# rgbboard.net
KiCad netlist of a schematic drawn in EAGLE
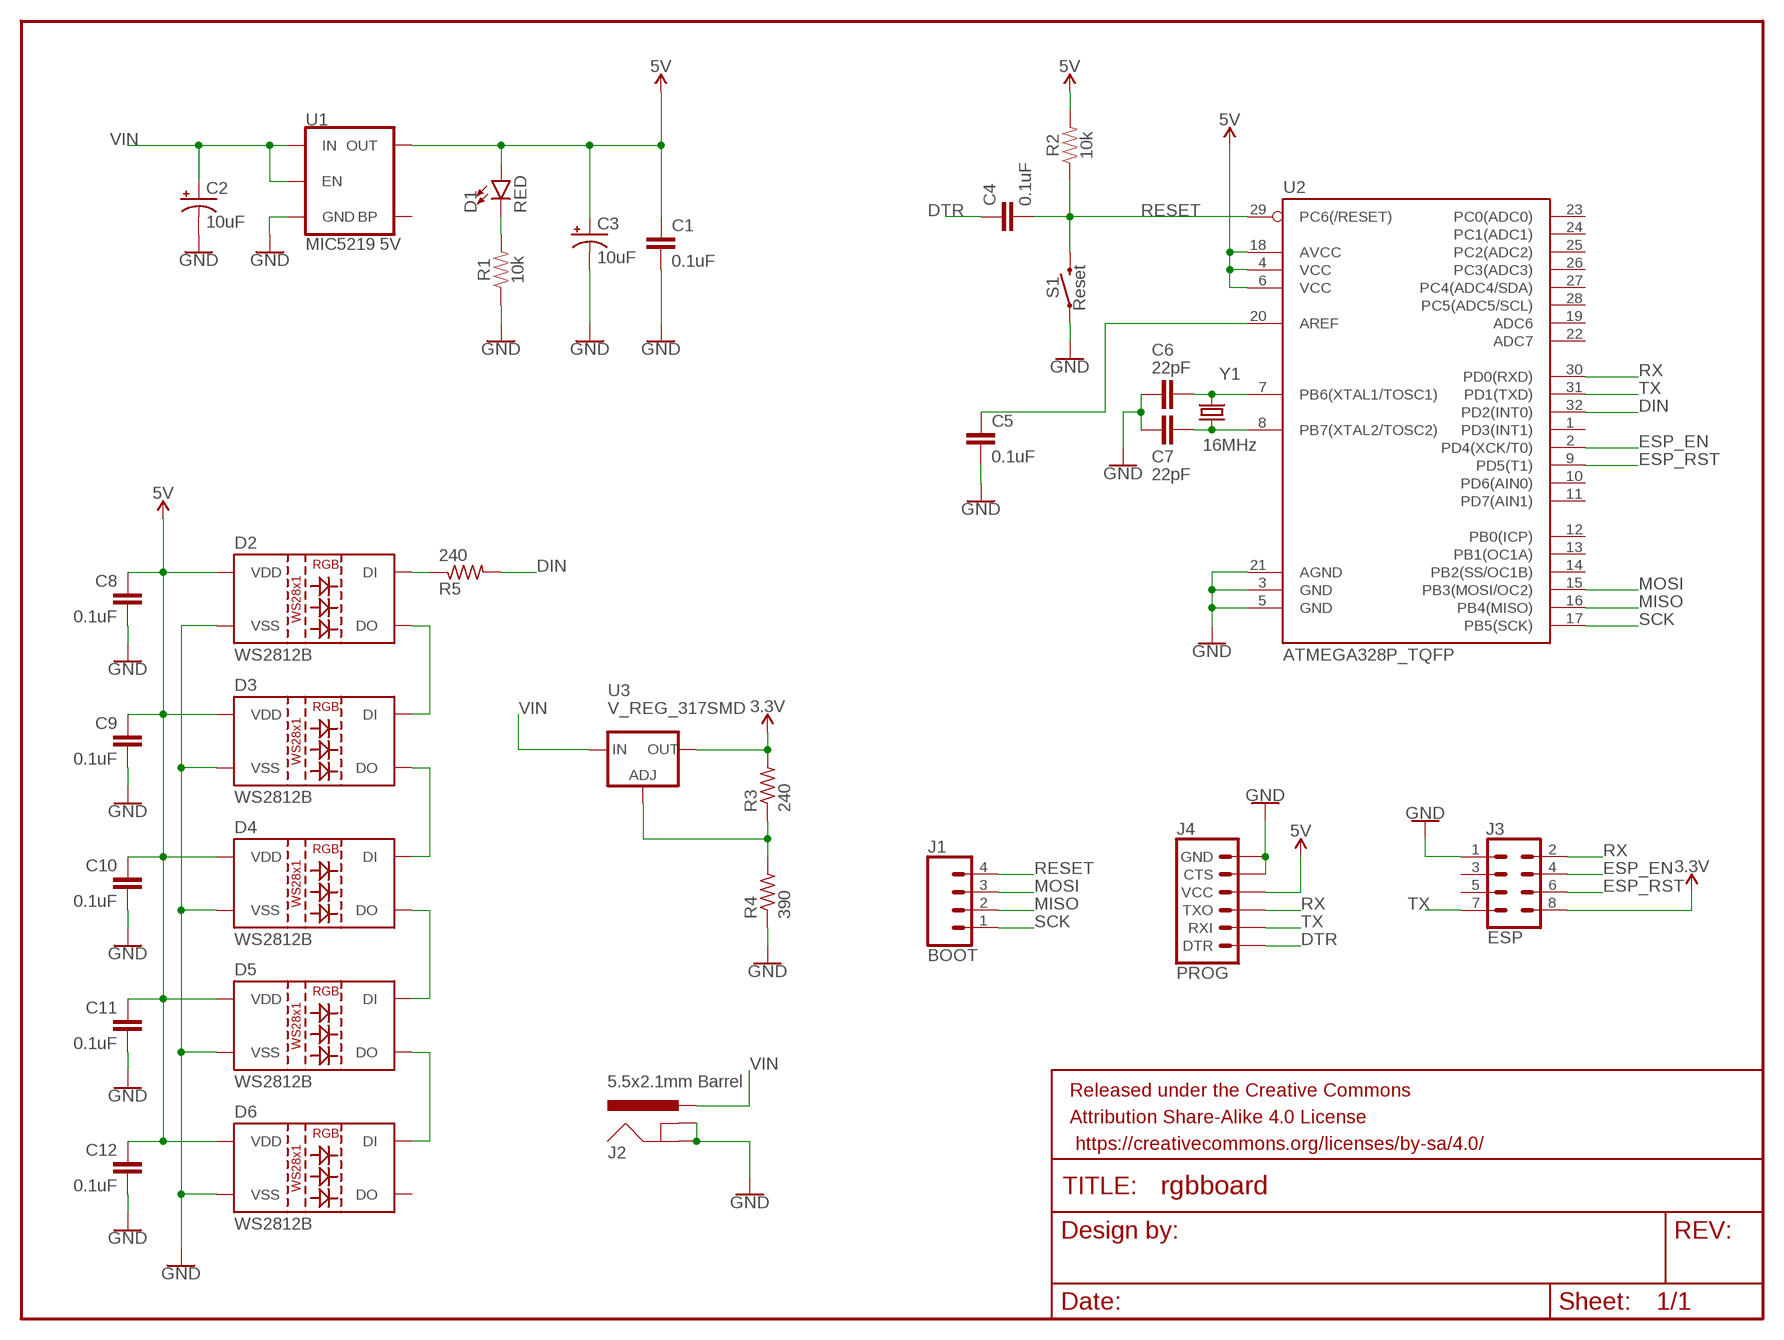
[diagram p0: schematic, sheet 1]

(export (version "E")
  (design (tool "Eeschema 10.0.6"))
  (components
    (comp (ref "C1")
      (value "0.1uF")
      (footprint "eagle-import:0603")
      (libsource (lib "eagle-import") (part "0.1UF-0603-25V-5%"))
    )
    (comp (ref "C2")
      (value "10uF")
      (footprint "eagle-import:EIA3216")
      (libsource (lib "eagle-import") (part "10UF-POLAR-EIA3216-16V-10%(TANT)"))
    )
    (comp (ref "C3")
      (value "10uF")
      (footprint "eagle-import:EIA3216")
      (libsource (lib "eagle-import") (part "10UF-POLAR-EIA3216-16V-10%(TANT)"))
    )
    (comp (ref "C4")
      (value "0.1uF")
      (footprint "eagle-import:0603")
      (libsource (lib "eagle-import") (part "0.1UF-0603-25V-5%"))
    )
    (comp (ref "C5")
      (value "0.1uF")
      (footprint "eagle-import:0603")
      (libsource (lib "eagle-import") (part "0.1UF-0603-25V-5%"))
    )
    (comp (ref "C6")
      (value "22pF")
      (footprint "eagle-import:0603")
      (libsource (lib "eagle-import") (part "22PF-0603-50V-5%"))
    )
    (comp (ref "C7")
      (value "22pF")
      (footprint "eagle-import:0603")
      (libsource (lib "eagle-import") (part "22PF-0603-50V-5%"))
    )
    (comp (ref "C8")
      (value "0.1uF")
      (footprint "eagle-import:0603")
      (libsource (lib "eagle-import") (part "0.1UF-0603-25V-5%"))
    )
    (comp (ref "C9")
      (value "0.1uF")
      (footprint "eagle-import:0603")
      (libsource (lib "eagle-import") (part "0.1UF-0603-25V-5%"))
    )
    (comp (ref "C10")
      (value "0.1uF")
      (footprint "eagle-import:0603")
      (libsource (lib "eagle-import") (part "0.1UF-0603-25V-5%"))
    )
    (comp (ref "C11")
      (value "0.1uF")
      (footprint "eagle-import:0603")
      (libsource (lib "eagle-import") (part "0.1UF-0603-25V-5%"))
    )
    (comp (ref "C12")
      (value "0.1uF")
      (footprint "eagle-import:0603")
      (libsource (lib "eagle-import") (part "0.1UF-0603-25V-5%"))
    )
    (comp (ref "D1")
      (value "RED")
      (footprint "eagle-import:LED-0603")
      (libsource (lib "eagle-import") (part "LED-RED0603"))
    )
    (comp (ref "D2")
      (value "WS2812B")
      (footprint "eagle-import:WS2812B")
      (libsource (lib "eagle-import") (part "WS2812B"))
    )
    (comp (ref "D3")
      (value "WS2812B")
      (footprint "eagle-import:WS2812B")
      (libsource (lib "eagle-import") (part "WS2812B"))
    )
    (comp (ref "D4")
      (value "WS2812B")
      (footprint "eagle-import:WS2812B")
      (libsource (lib "eagle-import") (part "WS2812B"))
    )
    (comp (ref "D5")
      (value "WS2812B")
      (footprint "eagle-import:WS2812B")
      (libsource (lib "eagle-import") (part "WS2812B"))
    )
    (comp (ref "D6")
      (value "WS2812B")
      (footprint "eagle-import:WS2812B")
      (libsource (lib "eagle-import") (part "WS2812B"))
    )
    (comp (ref "FRAME1")
      (value "FRAME-LETTER")
      (footprint "eagle-import:CREATIVE_COMMONS")
      (libsource (lib "eagle-import") (part "FRAME-LETTER"))
    )
    (comp (ref "J1")
      (value "BOOT")
      (footprint "eagle-import:1X04")
      (libsource (lib "eagle-import") (part "CONN_04"))
    )
    (comp (ref "J2")
      (value "5.5x2.1mm Barrel")
      (footprint "eagle-import:POWER_JACK_SMD")
      (libsource (lib "eagle-import") (part "POWER_JACKSMD"))
    )
    (comp (ref "J3")
      (value "ESP")
      (footprint "eagle-import:2X4")
      (libsource (lib "eagle-import") (part "CONN_04X2"))
    )
    (comp (ref "J4")
      (value "PROG")
      (footprint "eagle-import:1X06")
      (libsource (lib "eagle-import") (part "6_PIN_SERIAL_TARGET"))
    )
    (comp (ref "R1")
      (value "10k")
      (footprint "eagle-import:0603")
      (libsource (lib "eagle-import") (part "10KOHM-0603-1/10W-1%"))
    )
    (comp (ref "R2")
      (value "10k")
      (footprint "eagle-import:0603")
      (libsource (lib "eagle-import") (part "10KOHM-0603-1/10W-1%"))
    )
    (comp (ref "R3")
      (value "240")
      (footprint "eagle-import:R0603")
      (libsource (lib "eagle-import") (part "R-US_R0603"))
    )
    (comp (ref "R4")
      (value "390")
      (footprint "eagle-import:R0603")
      (libsource (lib "eagle-import") (part "R-US_R0603"))
    )
    (comp (ref "R5")
      (value "240")
      (footprint "eagle-import:R0603")
      (libsource (lib "eagle-import") (part "R-US_R0603"))
    )
    (comp (ref "S1")
      (value "Reset")
      (footprint "eagle-import:TACTILE_SWITCH_SMD_5.2MM")
      (libsource (lib "eagle-import") (part "MOMENTARY-SWITCH-SPST-SMD-5.2-REDUNDANT"))
    )
    (comp (ref "U1")
      (value "MIC5219 5V")
      (footprint "eagle-import:SOT23-5")
      (libsource (lib "eagle-import") (part "V_REG_MIC52195V"))
    )
    (comp (ref "U2")
      (value "ATMEGA328P_TQFP")
      (footprint "eagle-import:TQFP32-08")
      (libsource (lib "eagle-import") (part "ATMEGA328P_TQFP"))
    )
    (comp (ref "U3")
      (value "V_REG_317SMD")
      (footprint "eagle-import:SOT223")
      (libsource (lib "eagle-import") (part "V_REG_317SMD"))
    )
    (comp (ref "Y1")
      (value "16MHz")
      (footprint "eagle-import:CRYSTAL-SMD-5X3.2-4PAD")
      (libsource (lib "eagle-import") (part "CRYSTAL-16MHZSMD-5X3.2"))
    )
  )
  (nets
    (net (code "1") (name "/DIN") (class "Default")
      (node (ref "R5") (pin "2") (pinfunction "2_2") (pintype "passive"))
      (node (ref "U2") (pin "32") (pinfunction "PD2(INT0)_32") (pintype "bidirectional"))
    )
    (net (code "2") (name "/DTR") (class "Default")
      (node (ref "C4") (pin "1") (pinfunction "1_1") (pintype "passive"))
      (node (ref "J4") (pin "1") (pinfunction "DTR_1") (pintype "passive"))
    )
    (net (code "3") (name "/ESP_EN") (class "Default")
      (node (ref "J3") (pin "4") (pinfunction "4_4") (pintype "passive"))
      (node (ref "U2") (pin "2") (pinfunction "PD4(XCK/T0)_2") (pintype "bidirectional"))
    )
    (net (code "4") (name "/ESP_RST") (class "Default")
      (node (ref "J3") (pin "6") (pinfunction "6_6") (pintype "passive"))
      (node (ref "U2") (pin "9") (pinfunction "PD5(T1)_9") (pintype "bidirectional"))
    )
    (net (code "5") (name "/MISO") (class "Default")
      (node (ref "J1") (pin "2") (pinfunction "2_2") (pintype "passive"))
      (node (ref "U2") (pin "16") (pinfunction "PB4(MISO)_16") (pintype "bidirectional"))
    )
    (net (code "6") (name "/MOSI") (class "Default")
      (node (ref "J1") (pin "3") (pinfunction "3_3") (pintype "passive"))
      (node (ref "U2") (pin "15") (pinfunction "PB3(MOSI/OC2)_15") (pintype "bidirectional"))
    )
    (net (code "7") (name "/RESET") (class "Default")
      (node (ref "C4") (pin "2") (pinfunction "2_2") (pintype "passive"))
      (node (ref "J1") (pin "4") (pinfunction "4_4") (pintype "passive"))
      (node (ref "R2") (pin "1") (pinfunction "1_1") (pintype "passive"))
      (node (ref "S1") (pin "3") (pinfunction "2_3") (pintype "passive"))
      (node (ref "S1") (pin "4") (pinfunction "2_4") (pintype "passive"))
      (node (ref "U2") (pin "29") (pinfunction "PC6(/RESET)_29") (pintype "bidirectional"))
    )
    (net (code "8") (name "/RX") (class "Default")
      (node (ref "J3") (pin "2") (pinfunction "2_2") (pintype "passive"))
      (node (ref "J4") (pin "3") (pinfunction "TXO_3") (pintype "passive"))
      (node (ref "U2") (pin "30") (pinfunction "PD0(RXD)_30") (pintype "bidirectional"))
    )
    (net (code "9") (name "/SCK") (class "Default")
      (node (ref "J1") (pin "1") (pinfunction "1_1") (pintype "passive"))
      (node (ref "U2") (pin "17") (pinfunction "PB5(SCK)_17") (pintype "bidirectional"))
    )
    (net (code "10") (name "/TX") (class "Default")
      (node (ref "J3") (pin "7") (pinfunction "7_7") (pintype "passive"))
      (node (ref "J4") (pin "2") (pinfunction "RXI_2") (pintype "passive"))
      (node (ref "U2") (pin "31") (pinfunction "PD1(TXD)_31") (pintype "bidirectional"))
    )
    (net (code "11") (name "/VIN") (class "Default")
      (node (ref "C2") (pin "+") (pinfunction "+_+") (pintype "passive"))
      (node (ref "J2") (pin "VIN0") (pinfunction "PWR_VIN0") (pintype "bidirectional"))
      (node (ref "U1") (pin "1") (pinfunction "IN_1") (pintype "input"))
      (node (ref "U1") (pin "3") (pinfunction "EN_3") (pintype "input"))
      (node (ref "U3") (pin "3") (pinfunction "IN_3") (pintype "input"))
    )
    (net (code "12") (name "3.3V") (class "Default")
      (node (ref "J3") (pin "8") (pinfunction "8_8") (pintype "passive"))
      (node (ref "R3") (pin "2") (pinfunction "2_2") (pintype "passive"))
      (node (ref "U3") (pin "2") (pinfunction "OUT_2") (pintype "output"))
    )
    (net (code "13") (name "5V") (class "Default")
      (node (ref "C1") (pin "1") (pinfunction "1_1") (pintype "passive"))
      (node (ref "C10") (pin "1") (pinfunction "1_1") (pintype "passive"))
      (node (ref "C11") (pin "1") (pinfunction "1_1") (pintype "passive"))
      (node (ref "C12") (pin "1") (pinfunction "1_1") (pintype "passive"))
      (node (ref "C3") (pin "+") (pinfunction "+_+") (pintype "passive"))
      (node (ref "C8") (pin "1") (pinfunction "1_1") (pintype "passive"))
      (node (ref "C9") (pin "1") (pinfunction "1_1") (pintype "passive"))
      (node (ref "D1") (pin "A") (pinfunction "A_A") (pintype "passive"))
      (node (ref "D2") (pin "1") (pinfunction "VDD_1") (pintype "bidirectional"))
      (node (ref "D3") (pin "1") (pinfunction "VDD_1") (pintype "bidirectional"))
      (node (ref "D4") (pin "1") (pinfunction "VDD_1") (pintype "bidirectional"))
      (node (ref "D5") (pin "1") (pinfunction "VDD_1") (pintype "bidirectional"))
      (node (ref "D6") (pin "1") (pinfunction "VDD_1") (pintype "bidirectional"))
      (node (ref "J4") (pin "4") (pinfunction "VCC_4") (pintype "passive"))
      (node (ref "R2") (pin "2") (pinfunction "2_2") (pintype "passive"))
      (node (ref "U1") (pin "5") (pinfunction "OUT_5") (pintype "passive"))
      (node (ref "U2") (pin "18") (pinfunction "AVCC_18") (pintype "bidirectional"))
      (node (ref "U2") (pin "4") (pinfunction "VCC_4") (pintype "bidirectional"))
      (node (ref "U2") (pin "6") (pinfunction "VCC_6") (pintype "bidirectional"))
    )
    (net (code "14") (name "GND") (class "Default")
      (node (ref "C1") (pin "2") (pinfunction "2_2") (pintype "passive"))
      (node (ref "C10") (pin "2") (pinfunction "2_2") (pintype "passive"))
      (node (ref "C11") (pin "2") (pinfunction "2_2") (pintype "passive"))
      (node (ref "C12") (pin "2") (pinfunction "2_2") (pintype "passive"))
      (node (ref "C2") (pin "-") (pinfunction "-_-") (pintype "passive"))
      (node (ref "C3") (pin "-") (pinfunction "-_-") (pintype "passive"))
      (node (ref "C5") (pin "2") (pinfunction "2_2") (pintype "passive"))
      (node (ref "C6") (pin "1") (pinfunction "1_1") (pintype "passive"))
      (node (ref "C7") (pin "1") (pinfunction "1_1") (pintype "passive"))
      (node (ref "C8") (pin "2") (pinfunction "2_2") (pintype "passive"))
      (node (ref "C9") (pin "2") (pinfunction "2_2") (pintype "passive"))
      (node (ref "D2") (pin "3") (pinfunction "VSS_3") (pintype "bidirectional"))
      (node (ref "D3") (pin "3") (pinfunction "VSS_3") (pintype "bidirectional"))
      (node (ref "D4") (pin "3") (pinfunction "VSS_3") (pintype "bidirectional"))
      (node (ref "D5") (pin "3") (pinfunction "VSS_3") (pintype "bidirectional"))
      (node (ref "D6") (pin "3") (pinfunction "VSS_3") (pintype "bidirectional"))
      (node (ref "J2") (pin "GND") (pinfunction "GNDBREAK_GND") (pintype "bidirectional"))
      (node (ref "J2") (pin "P$4") (pinfunction "GND_P$4") (pintype "bidirectional"))
      (node (ref "J3") (pin "1") (pinfunction "1_1") (pintype "passive"))
      (node (ref "J4") (pin "5") (pinfunction "CTS_5") (pintype "passive"))
      (node (ref "J4") (pin "6") (pinfunction "GND_6") (pintype "passive"))
      (node (ref "R1") (pin "1") (pinfunction "1_1") (pintype "passive"))
      (node (ref "R4") (pin "1") (pinfunction "1_1") (pintype "passive"))
      (node (ref "S1") (pin "1") (pinfunction "1_1") (pintype "passive"))
      (node (ref "S1") (pin "2") (pinfunction "1_2") (pintype "passive"))
      (node (ref "U1") (pin "2") (pinfunction "GND_2") (pintype "input"))
      (node (ref "U2") (pin "21") (pinfunction "AGND_21") (pintype "bidirectional"))
      (node (ref "U2") (pin "3") (pinfunction "GND_3") (pintype "bidirectional"))
      (node (ref "U2") (pin "5") (pinfunction "GND_5") (pintype "bidirectional"))
    )
    (net (code "15") (name "Net-(D1-PadC)") (class "Default")
      (node (ref "D1") (pin "C") (pinfunction "C_C") (pintype "passive"))
      (node (ref "R1") (pin "2") (pinfunction "2_2") (pintype "passive"))
    )
    (net (code "16") (name "Net-(D2-DI)") (class "Default")
      (node (ref "D2") (pin "4") (pinfunction "DI_4") (pintype "bidirectional"))
      (node (ref "R5") (pin "1") (pinfunction "1_1") (pintype "passive"))
    )
    (net (code "17") (name "Net-(D2-DO)") (class "Default")
      (node (ref "D2") (pin "2") (pinfunction "DO_2") (pintype "bidirectional"))
      (node (ref "D3") (pin "4") (pinfunction "DI_4") (pintype "bidirectional"))
    )
    (net (code "18") (name "Net-(D3-DO)") (class "Default")
      (node (ref "D3") (pin "2") (pinfunction "DO_2") (pintype "bidirectional"))
      (node (ref "D4") (pin "4") (pinfunction "DI_4") (pintype "bidirectional"))
    )
    (net (code "19") (name "Net-(D4-DO)") (class "Default")
      (node (ref "D4") (pin "2") (pinfunction "DO_2") (pintype "bidirectional"))
      (node (ref "D5") (pin "4") (pinfunction "DI_4") (pintype "bidirectional"))
    )
    (net (code "20") (name "Net-(D5-DO)") (class "Default")
      (node (ref "D5") (pin "2") (pinfunction "DO_2") (pintype "bidirectional"))
      (node (ref "D6") (pin "4") (pinfunction "DI_4") (pintype "bidirectional"))
    )
    (net (code "21") (name "Net-(U2-AREF)") (class "Default")
      (node (ref "C5") (pin "1") (pinfunction "1_1") (pintype "passive"))
      (node (ref "U2") (pin "20") (pinfunction "AREF_20") (pintype "bidirectional"))
    )
    (net (code "22") (name "Net-(U2-PB6(XTAL1{slash}TOSC1))") (class "Default")
      (node (ref "C6") (pin "2") (pinfunction "2_2") (pintype "passive"))
      (node (ref "U2") (pin "7") (pinfunction "PB6(XTAL1/TOSC1)_7") (pintype "bidirectional"))
      (node (ref "Y1") (pin "3") (pinfunction "2_3") (pintype "passive"))
    )
    (net (code "23") (name "Net-(U2-PB7(XTAL2{slash}TOSC2))") (class "Default")
      (node (ref "C7") (pin "2") (pinfunction "2_2") (pintype "passive"))
      (node (ref "U2") (pin "8") (pinfunction "PB7(XTAL2/TOSC2)_8") (pintype "bidirectional"))
      (node (ref "Y1") (pin "1") (pinfunction "1_1") (pintype "passive"))
    )
    (net (code "24") (name "Net-(U3-ADJ)") (class "Default")
      (node (ref "R3") (pin "1") (pinfunction "1_1") (pintype "passive"))
      (node (ref "R4") (pin "2") (pinfunction "2_2") (pintype "passive"))
      (node (ref "U3") (pin "1") (pinfunction "ADJ_1") (pintype "input"))
    )
    (net (code "25") (name "unconnected-(D6-DO-Pad2)") (class "Default")
      (node (ref "D6") (pin "2") (pinfunction "DO_2") (pintype "bidirectional"))
    )
    (net (code "26") (name "unconnected-(J3-Pad3)") (class "Default")
      (node (ref "J3") (pin "3") (pinfunction "3_3") (pintype "passive"))
    )
    (net (code "27") (name "unconnected-(J3-Pad5)") (class "Default")
      (node (ref "J3") (pin "5") (pinfunction "5_5") (pintype "passive"))
    )
    (net (code "28") (name "unconnected-(U1-BP-Pad4)") (class "Default")
      (node (ref "U1") (pin "4") (pinfunction "BP_4") (pintype "input"))
    )
    (net (code "29") (name "unconnected-(U2-ADC6-Pad19)") (class "Default")
      (node (ref "U2") (pin "19") (pinfunction "ADC6_19") (pintype "bidirectional"))
    )
    (net (code "30") (name "unconnected-(U2-ADC7-Pad22)") (class "Default")
      (node (ref "U2") (pin "22") (pinfunction "ADC7_22") (pintype "bidirectional"))
    )
    (net (code "31") (name "unconnected-(U2-PB0(ICP)-Pad12)") (class "Default")
      (node (ref "U2") (pin "12") (pinfunction "PB0(ICP)_12") (pintype "bidirectional"))
    )
    (net (code "32") (name "unconnected-(U2-PB1(OC1A)-Pad13)") (class "Default")
      (node (ref "U2") (pin "13") (pinfunction "PB1(OC1A)_13") (pintype "bidirectional"))
    )
    (net (code "33") (name "unconnected-(U2-PB2(SS{slash}OC1B)-Pad14)") (class "Default")
      (node (ref "U2") (pin "14") (pinfunction "PB2(SS/OC1B)_14") (pintype "bidirectional"))
    )
    (net (code "34") (name "unconnected-(U2-PC0(ADC0)-Pad23)") (class "Default")
      (node (ref "U2") (pin "23") (pinfunction "PC0(ADC0)_23") (pintype "bidirectional"))
    )
    (net (code "35") (name "unconnected-(U2-PC1(ADC1)-Pad24)") (class "Default")
      (node (ref "U2") (pin "24") (pinfunction "PC1(ADC1)_24") (pintype "bidirectional"))
    )
    (net (code "36") (name "unconnected-(U2-PC2(ADC2)-Pad25)") (class "Default")
      (node (ref "U2") (pin "25") (pinfunction "PC2(ADC2)_25") (pintype "bidirectional"))
    )
    (net (code "37") (name "unconnected-(U2-PC3(ADC3)-Pad26)") (class "Default")
      (node (ref "U2") (pin "26") (pinfunction "PC3(ADC3)_26") (pintype "bidirectional"))
    )
    (net (code "38") (name "unconnected-(U2-PC4(ADC4{slash}SDA)-Pad27)") (class "Default")
      (node (ref "U2") (pin "27") (pinfunction "PC4(ADC4/SDA)_27") (pintype "bidirectional"))
    )
    (net (code "39") (name "unconnected-(U2-PC5(ADC5{slash}SCL)-Pad28)") (class "Default")
      (node (ref "U2") (pin "28") (pinfunction "PC5(ADC5/SCL)_28") (pintype "bidirectional"))
    )
    (net (code "40") (name "unconnected-(U2-PD3(INT1)-Pad1)") (class "Default")
      (node (ref "U2") (pin "1") (pinfunction "PD3(INT1)_1") (pintype "bidirectional"))
    )
    (net (code "41") (name "unconnected-(U2-PD6(AIN0)-Pad10)") (class "Default")
      (node (ref "U2") (pin "10") (pinfunction "PD6(AIN0)_10") (pintype "bidirectional"))
    )
    (net (code "42") (name "unconnected-(U2-PD7(AIN1)-Pad11)") (class "Default")
      (node (ref "U2") (pin "11") (pinfunction "PD7(AIN1)_11") (pintype "bidirectional"))
    )
  )
)
